# motorthing-v2.net
KiCad netlist of a schematic drawn in EAGLE
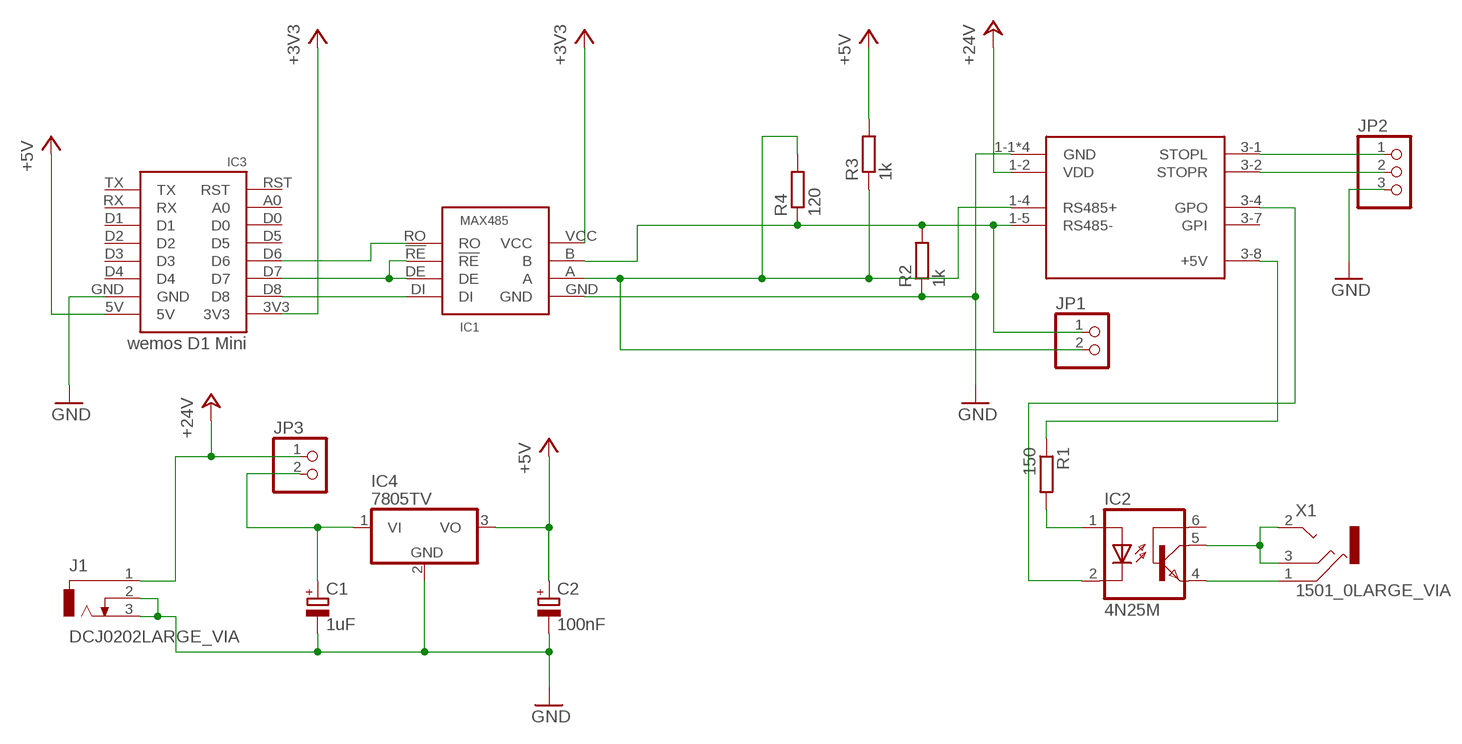
[diagram p0: schematic, sheet 1]

(export (version "E")
  (design (tool "Eeschema 10.0.6"))
  (components
    (comp (ref "C1")
      (value "1uF")
      (footprint "eagle-import:TT2D6")
      (libsource (lib "eagle-import") (part "CPOL-EUTT2D6"))
    )
    (comp (ref "C2")
      (value "100nF")
      (footprint "eagle-import:TT2D5")
      (libsource (lib "eagle-import") (part "CPOL-EUTT2D5"))
    )
    (comp (ref "IC1")
      (value "MAX485")
      (footprint "eagle-import:DIL08")
      (libsource (lib "eagle-import") (part "MAX485"))
    )
    (comp (ref "IC2")
      (value "4N25M")
      (footprint "eagle-import:DIL06")
      (fields (field (name "MPN") "4N25-M"))
      (libsource (lib "eagle-import") (part "4N?M25"))
    )
    (comp (ref "IC3")
      (value "wemos D1 Mini")
      (footprint "eagle-import:WEMOS-NOSILK")
      (libsource (lib "eagle-import") (part "WEMOSNOSILK"))
    )
    (comp (ref "IC4")
      (value "7805TV")
      (footprint "eagle-import:TO220V")
      (libsource (lib "eagle-import") (part "78TV05"))
    )
    (comp (ref "J1")
      (value "DCJ0202LARGE_VIA")
      (footprint "eagle-import:DCJ0202_LV")
      (libsource (lib "eagle-import") (part "DCJ0202LARGE_VIA"))
    )
    (comp (ref "JP1")
      (value "PINHD-1X2")
      (footprint "eagle-import:1X02")
      (libsource (lib "eagle-import") (part "PINHD-1X2"))
    )
    (comp (ref "JP2")
      (value "PINHD-1X3")
      (footprint "eagle-import:1X03")
      (libsource (lib "eagle-import") (part "PINHD-1X3"))
    )
    (comp (ref "JP3")
      (value "PINHD-1X2")
      (footprint "eagle-import:1X02")
      (libsource (lib "eagle-import") (part "PINHD-1X2"))
    )
    (comp (ref "R1")
      (value "150")
      (footprint "eagle-import:0207_10")
      (libsource (lib "eagle-import") (part "R-EU_0207/10"))
    )
    (comp (ref "R2")
      (value "1k")
      (footprint "eagle-import:0207_10")
      (libsource (lib "eagle-import") (part "R-EU_0207/10"))
    )
    (comp (ref "R3")
      (value "1k")
      (footprint "eagle-import:0207_10")
      (libsource (lib "eagle-import") (part "R-EU_0207/10"))
    )
    (comp (ref "R4")
      (value "120")
      (footprint "eagle-import:0207_10")
      (libsource (lib "eagle-import") (part "R-EU_0207/10"))
    )
    (comp (ref "TMCM-110")
      (value "TMCM-110")
      (footprint "eagle-import:TMCM-110")
      (libsource (lib "eagle-import") (part "TMCM-110"))
    )
    (comp (ref "X1")
      (value "1501_0LARGE_VIA")
      (footprint "eagle-import:1501_05_LV")
      (libsource (lib "eagle-import") (part "1501_0LARGE_VIA"))
    )
  )
  (nets
    (net (code "1") (name "+3V3") (class "Default")
      (node (ref "IC1") (pin "VCC") (pinfunction "VCC_VCC") (pintype "bidirectional"))
      (node (ref "IC3") (pin "3V3") (pinfunction "3V3_3V3") (pintype "bidirectional"))
    )
    (net (code "2") (name "+5V") (class "Default")
      (node (ref "C2") (pin "+") (pinfunction "+_+") (pintype "passive"))
      (node (ref "IC3") (pin "5V") (pinfunction "5V_5V") (pintype "bidirectional"))
      (node (ref "IC4") (pin "3") (pinfunction "VO_3") (pintype "passive"))
      (node (ref "R3") (pin "2") (pinfunction "2_2") (pintype "passive"))
    )
    (net (code "3") (name "+24V") (class "Default")
      (node (ref "J1") (pin "1") (pinfunction "1_1") (pintype "passive"))
      (node (ref "JP3") (pin "1") (pinfunction "1_1") (pintype "passive"))
      (node (ref "TMCM-110") (pin "1-2") (pinfunction "VDD_1-2") (pintype "bidirectional"))
    )
    (net (code "4") (name "GND") (class "Default")
      (node (ref "C1") (pin "-") (pinfunction "-_-") (pintype "passive"))
      (node (ref "C2") (pin "-") (pinfunction "-_-") (pintype "passive"))
      (node (ref "IC1") (pin "GND") (pinfunction "GND_GND") (pintype "bidirectional"))
      (node (ref "IC3") (pin "GND") (pinfunction "GND_GND") (pintype "bidirectional"))
      (node (ref "IC4") (pin "2") (pinfunction "GND_2") (pintype "passive"))
      (node (ref "J1") (pin "2") (pinfunction "2_2") (pintype "passive"))
      (node (ref "J1") (pin "3") (pinfunction "3_3") (pintype "passive"))
      (node (ref "JP2") (pin "3") (pinfunction "3_3") (pintype "passive"))
      (node (ref "R2") (pin "1") (pinfunction "1_1") (pintype "passive"))
      (node (ref "TMCM-110") (pin "1-1") (pinfunction "GND_1-1") (pintype "bidirectional"))
      (node (ref "TMCM-110") (pin "1-3") (pinfunction "GND_1-3") (pintype "bidirectional"))
      (node (ref "TMCM-110") (pin "3-3") (pinfunction "GND_3-3") (pintype "bidirectional"))
      (node (ref "TMCM-110") (pin "3-6") (pinfunction "GND_3-6") (pintype "bidirectional"))
    )
    (net (code "5") (name "Net-(IC1-PadDI)") (class "Default")
      (node (ref "IC1") (pin "DI") (pinfunction "DI_DI") (pintype "bidirectional"))
      (node (ref "IC3") (pin "D8") (pinfunction "D8_D8") (pintype "bidirectional"))
    )
    (net (code "6") (name "Net-(IC1-PadRO)") (class "Default")
      (node (ref "IC1") (pin "RO") (pinfunction "RO_RO") (pintype "bidirectional"))
      (node (ref "IC3") (pin "D6") (pinfunction "D6_D6") (pintype "bidirectional"))
    )
    (net (code "7") (name "Net-(IC1-~{RE})") (class "Default")
      (node (ref "IC1") (pin "!RE") (pinfunction "~{RE}_!RE") (pintype "bidirectional"))
      (node (ref "IC1") (pin "DE") (pinfunction "DE_DE") (pintype "bidirectional"))
      (node (ref "IC3") (pin "D7") (pinfunction "D7_D7") (pintype "bidirectional"))
    )
    (net (code "8") (name "Net-(IC2-A)") (class "Default")
      (node (ref "IC2") (pin "1") (pinfunction "A_1") (pintype "passive"))
      (node (ref "R1") (pin "2") (pinfunction "2_2") (pintype "passive"))
    )
    (net (code "9") (name "Net-(IC2-C)") (class "Default")
      (node (ref "IC2") (pin "2") (pinfunction "C_2") (pintype "passive"))
      (node (ref "TMCM-110") (pin "3-4") (pinfunction "GPO_3-4") (pintype "bidirectional"))
    )
    (net (code "10") (name "Net-(IC2-COL)") (class "Default")
      (node (ref "IC2") (pin "5") (pinfunction "COL_5") (pintype "passive"))
      (node (ref "X1") (pin "2") (pinfunction "2_2") (pintype "passive"))
      (node (ref "X1") (pin "3") (pinfunction "3_3") (pintype "passive"))
    )
    (net (code "11") (name "Net-(IC2-EMI)") (class "Default")
      (node (ref "IC2") (pin "4") (pinfunction "EMI_4") (pintype "passive"))
      (node (ref "X1") (pin "1") (pinfunction "1_1") (pintype "passive"))
    )
    (net (code "12") (name "Net-(IC4-VI)") (class "Default")
      (node (ref "C1") (pin "+") (pinfunction "+_+") (pintype "passive"))
      (node (ref "IC4") (pin "1") (pinfunction "VI_1") (pintype "input"))
      (node (ref "JP3") (pin "2") (pinfunction "2_2") (pintype "passive"))
    )
    (net (code "13") (name "Net-(TMCM-110-+5V)") (class "Default")
      (node (ref "R1") (pin "1") (pinfunction "1_1") (pintype "passive"))
      (node (ref "TMCM-110") (pin "3-8") (pinfunction "+5V_3-8") (pintype "bidirectional"))
    )
    (net (code "14") (name "Net-(TMCM-110-RS485+)") (class "Default")
      (node (ref "IC1") (pin "A") (pinfunction "A_A") (pintype "bidirectional"))
      (node (ref "JP1") (pin "2") (pinfunction "2_2") (pintype "passive"))
      (node (ref "R3") (pin "1") (pinfunction "1_1") (pintype "passive"))
      (node (ref "R4") (pin "2") (pinfunction "2_2") (pintype "passive"))
      (node (ref "TMCM-110") (pin "1-4") (pinfunction "RS485+_1-4") (pintype "bidirectional"))
    )
    (net (code "15") (name "Net-(TMCM-110-RS485-)") (class "Default")
      (node (ref "IC1") (pin "B") (pinfunction "B_B") (pintype "bidirectional"))
      (node (ref "JP1") (pin "1") (pinfunction "1_1") (pintype "passive"))
      (node (ref "R2") (pin "2") (pinfunction "2_2") (pintype "passive"))
      (node (ref "R4") (pin "1") (pinfunction "1_1") (pintype "passive"))
      (node (ref "TMCM-110") (pin "1-5") (pinfunction "RS485-_1-5") (pintype "bidirectional"))
    )
    (net (code "16") (name "Net-(TMCM-110-STOPL)") (class "Default")
      (node (ref "JP2") (pin "1") (pinfunction "1_1") (pintype "passive"))
      (node (ref "TMCM-110") (pin "3-1") (pinfunction "STOPL_3-1") (pintype "bidirectional"))
    )
    (net (code "17") (name "Net-(TMCM-110-STOPR)") (class "Default")
      (node (ref "JP2") (pin "2") (pinfunction "2_2") (pintype "passive"))
      (node (ref "TMCM-110") (pin "3-2") (pinfunction "STOPR_3-2") (pintype "bidirectional"))
    )
    (net (code "18") (name "unconnected-(IC2-BAS-Pad6)") (class "Default")
      (node (ref "IC2") (pin "6") (pinfunction "BAS_6") (pintype "passive"))
    )
    (net (code "19") (name "unconnected-(IC3-PadA0)") (class "Default")
      (node (ref "IC3") (pin "A0") (pinfunction "A0_A0") (pintype "bidirectional"))
    )
    (net (code "20") (name "unconnected-(IC3-PadD0)") (class "Default")
      (node (ref "IC3") (pin "D0") (pinfunction "D0_D0") (pintype "bidirectional"))
    )
    (net (code "21") (name "unconnected-(IC3-PadD1)") (class "Default")
      (node (ref "IC3") (pin "D1") (pinfunction "D1_D1") (pintype "bidirectional"))
    )
    (net (code "22") (name "unconnected-(IC3-PadD2)") (class "Default")
      (node (ref "IC3") (pin "D2") (pinfunction "D2_D2") (pintype "bidirectional"))
    )
    (net (code "23") (name "unconnected-(IC3-PadD3)") (class "Default")
      (node (ref "IC3") (pin "D3") (pinfunction "D3_D3") (pintype "bidirectional"))
    )
    (net (code "24") (name "unconnected-(IC3-PadD4)") (class "Default")
      (node (ref "IC3") (pin "D4") (pinfunction "D4_D4") (pintype "bidirectional"))
    )
    (net (code "25") (name "unconnected-(IC3-PadD5)") (class "Default")
      (node (ref "IC3") (pin "D5") (pinfunction "D5_D5") (pintype "bidirectional"))
    )
    (net (code "26") (name "unconnected-(IC3-PadRST)") (class "Default")
      (node (ref "IC3") (pin "RST") (pinfunction "RST_RST") (pintype "bidirectional"))
    )
    (net (code "27") (name "unconnected-(IC3-PadRX)") (class "Default")
      (node (ref "IC3") (pin "RX") (pinfunction "RX_RX") (pintype "bidirectional"))
    )
    (net (code "28") (name "unconnected-(IC3-PadTX)") (class "Default")
      (node (ref "IC3") (pin "TX") (pinfunction "TX_TX") (pintype "bidirectional"))
    )
    (net (code "29") (name "unconnected-(TMCM-110-GPI-Pad3-7)") (class "Default")
      (node (ref "TMCM-110") (pin "3-7") (pinfunction "GPI_3-7") (pintype "bidirectional"))
    )
  )
)
